# Block_Diagram.net
KiCad netlist of a schematic drawn in Altium Designer
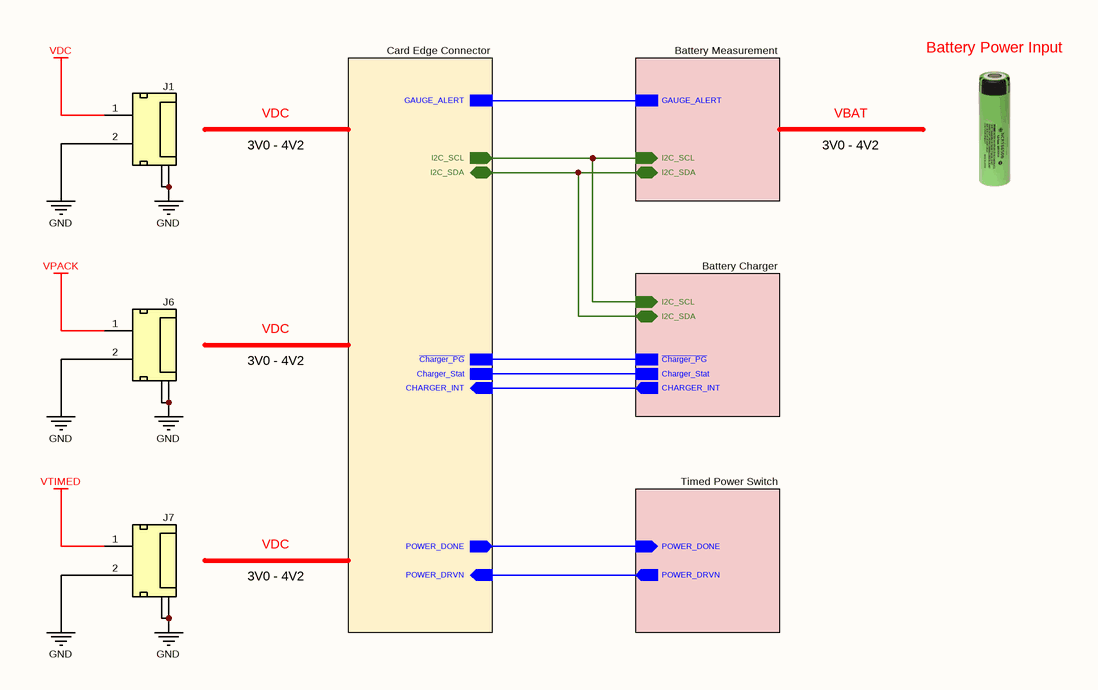
[diagram p0: Block Diagram.SchDoc]

(export (version "E")
  (design (tool "Eeschema 10.0.6"))
  (components
    (comp (ref "J1")
      (value "2P SMD Tunic Connector")
      (footprint "Connector_Tunic 2P")
      (description "Mini Tunic Connector with 2P")
      (fields
        (field (name "MANUFACTURER PART NUMBER") "53261-0271")
        (field (name "MOUSER PART NUMBER") "538-53261-0271")
      )
      (libsource (lib "P101DA_Library") (part "Connector - Mini Tunic 2P (1.25)"))
    )
    (comp (ref "J6")
      (value "2P SMD Tunic Connector")
      (footprint "Connector_Tunic 2P")
      (description "Mini Tunic Connector with 2P")
      (fields
        (field (name "MANUFACTURER PART NUMBER") "53261-0271")
        (field (name "MOUSER PART NUMBER") "538-53261-0271")
      )
      (libsource (lib "P101DA_Library") (part "Connector - Mini Tunic 2P (1.25)"))
    )
    (comp (ref "J7")
      (value "2P SMD Tunic Connector")
      (footprint "Connector_Tunic 2P")
      (description "Mini Tunic Connector with 2P")
      (fields
        (field (name "MANUFACTURER PART NUMBER") "53261-0271")
        (field (name "MOUSER PART NUMBER") "538-53261-0271")
      )
      (libsource (lib "P101DA_Library") (part "Connector - Mini Tunic 2P (1.25)"))
    )
  )
  (nets
    (net (code "9") (name "GND") (class "Default")
      (node (ref "J1") (pin "2") (pinfunction "Pin2_2") (pintype "passive"))
      (node (ref "J1") (pin "3") (pinfunction "GND_3") (pintype "passive"))
      (node (ref "J1") (pin "4") (pinfunction "GND_4") (pintype "passive"))
      (node (ref "J6") (pin "2") (pinfunction "Pin2_2") (pintype "passive"))
      (node (ref "J6") (pin "3") (pinfunction "GND_3") (pintype "passive"))
      (node (ref "J6") (pin "4") (pinfunction "GND_4") (pintype "passive"))
      (node (ref "J7") (pin "2") (pinfunction "Pin2_2") (pintype "passive"))
      (node (ref "J7") (pin "3") (pinfunction "GND_3") (pintype "passive"))
      (node (ref "J7") (pin "4") (pinfunction "GND_4") (pintype "passive"))
    )
    (net (code "10") (name "VDC") (class "Default")
      (node (ref "J1") (pin "1") (pinfunction "Pin1_1") (pintype "passive"))
    )
    (net (code "11") (name "VPACK") (class "Default")
      (node (ref "J6") (pin "1") (pinfunction "Pin1_1") (pintype "passive"))
    )
    (net (code "12") (name "VTIMED") (class "Default")
      (node (ref "J7") (pin "1") (pinfunction "Pin1_1") (pintype "passive"))
    )
  )
)
